# CPU.net
KiCad netlist of a schematic drawn in Altium Designer
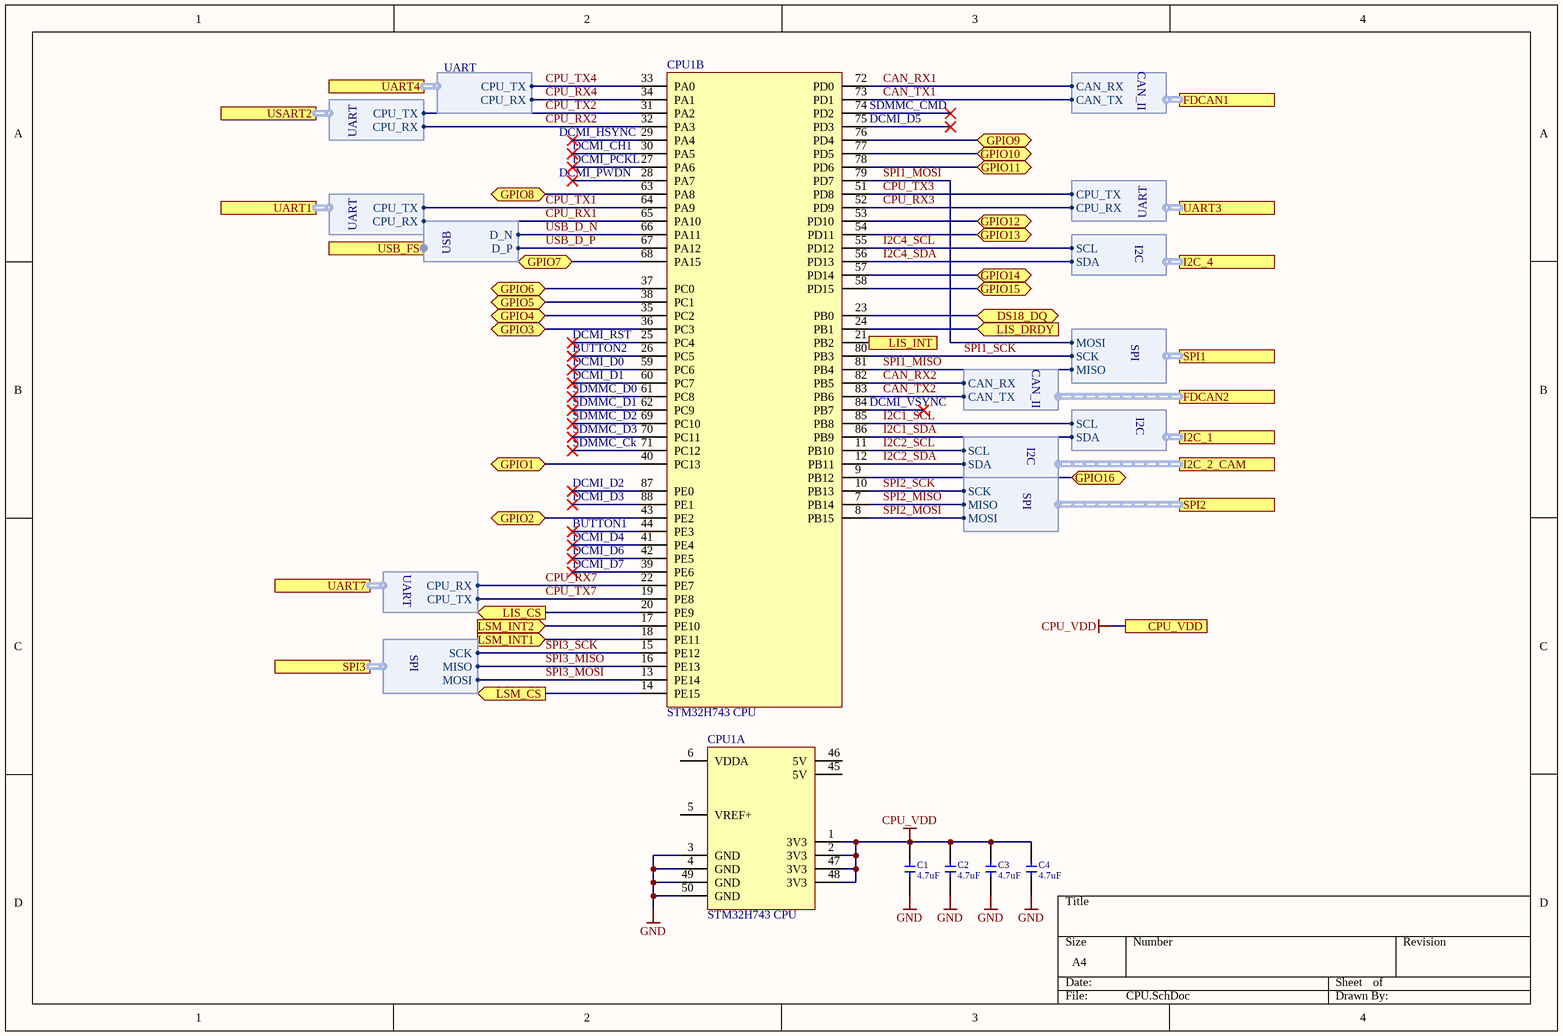
[diagram p0: CPU.SchDoc]

(export (version "E")
  (design (tool "Eeschema 10.0.6"))
  (components
    (comp (ref "C1")
      (value "4.7uF")
      (footprint "CERCAP 0603")
      (description "Capacitor")
      (fields (field (name "Comment") "CERCAP 0603 4.7uF * X7R"))
      (libsource (lib "!main") (part "!Capacitor"))
    )
    (comp (ref "C2")
      (value "4.7uF")
      (footprint "CERCAP 0603")
      (description "Capacitor")
      (fields (field (name "Comment") "CERCAP 0603 4.7uF * X7R"))
      (libsource (lib "!main") (part "!Capacitor"))
    )
    (comp (ref "C3")
      (value "4.7uF")
      (footprint "CERCAP 0603")
      (description "Capacitor")
      (fields (field (name "Comment") "CERCAP 0603 4.7uF * X7R"))
      (libsource (lib "!main") (part "!Capacitor"))
    )
    (comp (ref "C4")
      (value "4.7uF")
      (footprint "CERCAP 0603")
      (description "Capacitor")
      (fields (field (name "Comment") "CERCAP 0603 4.7uF * X7R"))
      (libsource (lib "!main") (part "!Capacitor"))
    )
    (comp (ref "CPU1")
      (value "STM32H743 CPU")
      (footprint "STM32H7_CPU")
      (description "STM32H743 processor module")
      (libsource (lib "modules") (part "STM32H7 CPU"))
    )
  )
  (nets
    (net (code "6") (name "/CAN_RX1") (class "Default")
      (node (ref "CPU1") (pin "72") (pinfunction "PD0_72") (pintype "passive"))
    )
    (net (code "7") (name "/CAN_RX2") (class "Default")
      (node (ref "CPU1") (pin "82") (pinfunction "PB5_82") (pintype "passive"))
    )
    (net (code "8") (name "/CAN_TX1") (class "Default")
      (node (ref "CPU1") (pin "73") (pinfunction "PD1_73") (pintype "passive"))
    )
    (net (code "9") (name "/CAN_TX2") (class "Default")
      (node (ref "CPU1") (pin "83") (pinfunction "PB6_83") (pintype "passive"))
    )
    (net (code "10") (name "/CPU_RX1") (class "Default")
      (node (ref "CPU1") (pin "65") (pinfunction "PA10_65") (pintype "passive"))
    )
    (net (code "11") (name "/CPU_RX2") (class "Default")
      (node (ref "CPU1") (pin "32") (pinfunction "PA3_32") (pintype "passive"))
    )
    (net (code "12") (name "/CPU_RX3") (class "Default")
      (node (ref "CPU1") (pin "52") (pinfunction "PD9_52") (pintype "passive"))
    )
    (net (code "13") (name "/CPU_RX4") (class "Default")
      (node (ref "CPU1") (pin "34") (pinfunction "PA1_34") (pintype "passive"))
    )
    (net (code "14") (name "/CPU_RX7") (class "Default")
      (node (ref "CPU1") (pin "22") (pinfunction "PE7_22") (pintype "passive"))
    )
    (net (code "15") (name "/CPU_TX1") (class "Default")
      (node (ref "CPU1") (pin "64") (pinfunction "PA9_64") (pintype "passive"))
    )
    (net (code "16") (name "/CPU_TX2") (class "Default")
      (node (ref "CPU1") (pin "31") (pinfunction "PA2_31") (pintype "passive"))
    )
    (net (code "17") (name "/CPU_TX3") (class "Default")
      (node (ref "CPU1") (pin "51") (pinfunction "PD8_51") (pintype "passive"))
    )
    (net (code "18") (name "/CPU_TX4") (class "Default")
      (node (ref "CPU1") (pin "33") (pinfunction "PA0_33") (pintype "passive"))
    )
    (net (code "19") (name "/CPU_TX7") (class "Default")
      (node (ref "CPU1") (pin "19") (pinfunction "PE8_19") (pintype "passive"))
    )
    (net (code "20") (name "/DS18_DQ") (class "Default")
      (node (ref "CPU1") (pin "23") (pinfunction "PB0_23") (pintype "passive"))
    )
    (net (code "21") (name "/GPIO1") (class "Default")
      (node (ref "CPU1") (pin "40") (pinfunction "PC13_40") (pintype "passive"))
    )
    (net (code "22") (name "/GPIO2") (class "Default")
      (node (ref "CPU1") (pin "43") (pinfunction "PE2_43") (pintype "passive"))
    )
    (net (code "23") (name "/GPIO3") (class "Default")
      (node (ref "CPU1") (pin "36") (pinfunction "PC3_36") (pintype "passive"))
    )
    (net (code "24") (name "/GPIO4") (class "Default")
      (node (ref "CPU1") (pin "35") (pinfunction "PC2_35") (pintype "passive"))
    )
    (net (code "25") (name "/GPIO5") (class "Default")
      (node (ref "CPU1") (pin "38") (pinfunction "PC1_38") (pintype "passive"))
    )
    (net (code "26") (name "/GPIO6") (class "Default")
      (node (ref "CPU1") (pin "37") (pinfunction "PC0_37") (pintype "passive"))
    )
    (net (code "27") (name "/GPIO7") (class "Default")
      (node (ref "CPU1") (pin "68") (pinfunction "PA15_68") (pintype "passive"))
    )
    (net (code "28") (name "/GPIO8") (class "Default")
      (node (ref "CPU1") (pin "63") (pinfunction "PA8_63") (pintype "passive"))
    )
    (net (code "29") (name "/GPIO9") (class "Default")
      (node (ref "CPU1") (pin "76") (pinfunction "PD4_76") (pintype "passive"))
    )
    (net (code "30") (name "/GPIO10") (class "Default")
      (node (ref "CPU1") (pin "77") (pinfunction "PD5_77") (pintype "passive"))
    )
    (net (code "31") (name "/GPIO11") (class "Default")
      (node (ref "CPU1") (pin "78") (pinfunction "PD6_78") (pintype "passive"))
    )
    (net (code "32") (name "/GPIO12") (class "Default")
      (node (ref "CPU1") (pin "53") (pinfunction "PD10_53") (pintype "passive"))
    )
    (net (code "33") (name "/GPIO13") (class "Default")
      (node (ref "CPU1") (pin "54") (pinfunction "PD11_54") (pintype "passive"))
    )
    (net (code "34") (name "/GPIO14") (class "Default")
      (node (ref "CPU1") (pin "57") (pinfunction "PD14_57") (pintype "passive"))
    )
    (net (code "35") (name "/GPIO15") (class "Default")
      (node (ref "CPU1") (pin "58") (pinfunction "PD15_58") (pintype "passive"))
    )
    (net (code "36") (name "/GPIO16") (class "Default")
      (node (ref "CPU1") (pin "9") (pinfunction "PB12_9") (pintype "passive"))
    )
    (net (code "37") (name "/I2C1_SCL") (class "Default")
      (node (ref "CPU1") (pin "85") (pinfunction "PB8_85") (pintype "passive"))
    )
    (net (code "38") (name "/I2C1_SDA") (class "Default")
      (node (ref "CPU1") (pin "86") (pinfunction "PB9_86") (pintype "passive"))
    )
    (net (code "39") (name "/I2C2_SCL") (class "Default")
      (node (ref "CPU1") (pin "11") (pinfunction "PB10_11") (pintype "passive"))
    )
    (net (code "40") (name "/I2C2_SDA") (class "Default")
      (node (ref "CPU1") (pin "12") (pinfunction "PB11_12") (pintype "passive"))
    )
    (net (code "41") (name "/I2C4_SCL") (class "Default")
      (node (ref "CPU1") (pin "55") (pinfunction "PD12_55") (pintype "passive"))
    )
    (net (code "42") (name "/I2C4_SDA") (class "Default")
      (node (ref "CPU1") (pin "56") (pinfunction "PD13_56") (pintype "passive"))
    )
    (net (code "43") (name "/LIS_CS") (class "Default")
      (node (ref "CPU1") (pin "20") (pinfunction "PE9_20") (pintype "passive"))
    )
    (net (code "44") (name "/LIS_DRDY") (class "Default")
      (node (ref "CPU1") (pin "24") (pinfunction "PB1_24") (pintype "passive"))
    )
    (net (code "45") (name "/LIS_INT") (class "Default")
      (node (ref "CPU1") (pin "21") (pinfunction "PB2_21") (pintype "passive"))
    )
    (net (code "46") (name "/LSM_CS") (class "Default")
      (node (ref "CPU1") (pin "14") (pinfunction "PE15_14") (pintype "passive"))
    )
    (net (code "47") (name "/LSM_INT1") (class "Default")
      (node (ref "CPU1") (pin "18") (pinfunction "PE11_18") (pintype "passive"))
    )
    (net (code "48") (name "/LSM_INT2") (class "Default")
      (node (ref "CPU1") (pin "17") (pinfunction "PE10_17") (pintype "passive"))
    )
    (net (code "49") (name "/SPI1_MISO") (class "Default")
      (node (ref "CPU1") (pin "81") (pinfunction "PB4_81") (pintype "passive"))
    )
    (net (code "50") (name "/SPI1_MOSI") (class "Default")
      (node (ref "CPU1") (pin "79") (pinfunction "PD7_79") (pintype "passive"))
    )
    (net (code "51") (name "/SPI1_SCK") (class "Default")
      (node (ref "CPU1") (pin "80") (pinfunction "PB3_80") (pintype "passive"))
    )
    (net (code "52") (name "/SPI2_MISO") (class "Default")
      (node (ref "CPU1") (pin "7") (pinfunction "PB14_7") (pintype "passive"))
    )
    (net (code "53") (name "/SPI2_MOSI") (class "Default")
      (node (ref "CPU1") (pin "8") (pinfunction "PB15_8") (pintype "passive"))
    )
    (net (code "54") (name "/SPI2_SCK") (class "Default")
      (node (ref "CPU1") (pin "10") (pinfunction "PB13_10") (pintype "passive"))
    )
    (net (code "55") (name "/SPI3_MISO") (class "Default")
      (node (ref "CPU1") (pin "16") (pinfunction "PE13_16") (pintype "passive"))
    )
    (net (code "56") (name "/SPI3_MOSI") (class "Default")
      (node (ref "CPU1") (pin "13") (pinfunction "PE14_13") (pintype "passive"))
    )
    (net (code "57") (name "/SPI3_SCK") (class "Default")
      (node (ref "CPU1") (pin "15") (pinfunction "PE12_15") (pintype "passive"))
    )
    (net (code "58") (name "/USB_D_N") (class "Default")
      (node (ref "CPU1") (pin "66") (pinfunction "PA11_66") (pintype "passive"))
    )
    (net (code "59") (name "/USB_D_P") (class "Default")
      (node (ref "CPU1") (pin "67") (pinfunction "PA12_67") (pintype "passive"))
    )
    (net (code "65") (name "CPU_VDD") (class "Default")
      (node (ref "C1") (pin "2") (pintype "passive"))
      (node (ref "C2") (pin "2") (pintype "passive"))
      (node (ref "C3") (pin "2") (pintype "passive"))
      (node (ref "C4") (pin "2") (pintype "passive"))
      (node (ref "CPU1") (pin "1") (pinfunction "3V3_1") (pintype "passive"))
      (node (ref "CPU1") (pin "2") (pinfunction "3V3_2") (pintype "passive"))
      (node (ref "CPU1") (pin "47") (pinfunction "3V3_47") (pintype "passive"))
      (node (ref "CPU1") (pin "48") (pinfunction "3V3_48") (pintype "passive"))
    )
    (net (code "66") (name "GND") (class "Default")
      (node (ref "C1") (pin "1") (pintype "passive"))
      (node (ref "C2") (pin "1") (pintype "passive"))
      (node (ref "C3") (pin "1") (pintype "passive"))
      (node (ref "C4") (pin "1") (pintype "passive"))
      (node (ref "CPU1") (pin "3") (pinfunction "GND_3") (pintype "passive"))
      (node (ref "CPU1") (pin "4") (pinfunction "GND_4") (pintype "passive"))
      (node (ref "CPU1") (pin "49") (pinfunction "GND_49") (pintype "passive"))
      (node (ref "CPU1") (pin "50") (pinfunction "GND_50") (pintype "passive"))
    )
    (net (code "67") (name "unconnected-(CPU1A-5V-Pad45)") (class "Default")
      (node (ref "CPU1") (pin "45") (pinfunction "5V_45") (pintype "passive"))
    )
    (net (code "68") (name "unconnected-(CPU1A-5V-Pad46)") (class "Default")
      (node (ref "CPU1") (pin "46") (pinfunction "5V_46") (pintype "passive"))
    )
    (net (code "69") (name "unconnected-(CPU1A-VDDA-Pad6)") (class "Default")
      (node (ref "CPU1") (pin "6") (pinfunction "VDDA_6") (pintype "passive"))
    )
    (net (code "70") (name "unconnected-(CPU1A-VREF+-Pad5)") (class "Default")
      (node (ref "CPU1") (pin "5") (pinfunction "VREF+_5") (pintype "passive"))
    )
    (net (code "71") (name "unconnected-(CPU1B-PA4-Pad29)") (class "Default")
      (node (ref "CPU1") (pin "29") (pinfunction "PA4_29") (pintype "passive+no_connect"))
    )
    (net (code "72") (name "unconnected-(CPU1B-PA5-Pad30)") (class "Default")
      (node (ref "CPU1") (pin "30") (pinfunction "PA5_30") (pintype "passive+no_connect"))
    )
    (net (code "73") (name "unconnected-(CPU1B-PA6-Pad27)") (class "Default")
      (node (ref "CPU1") (pin "27") (pinfunction "PA6_27") (pintype "passive+no_connect"))
    )
    (net (code "74") (name "unconnected-(CPU1B-PA7-Pad28)") (class "Default")
      (node (ref "CPU1") (pin "28") (pinfunction "PA7_28") (pintype "passive+no_connect"))
    )
    (net (code "75") (name "unconnected-(CPU1B-PB7-Pad84)") (class "Default")
      (node (ref "CPU1") (pin "84") (pinfunction "PB7_84") (pintype "passive+no_connect"))
    )
    (net (code "76") (name "unconnected-(CPU1B-PC4-Pad25)") (class "Default")
      (node (ref "CPU1") (pin "25") (pinfunction "PC4_25") (pintype "passive+no_connect"))
    )
    (net (code "77") (name "unconnected-(CPU1B-PC5-Pad26)") (class "Default")
      (node (ref "CPU1") (pin "26") (pinfunction "PC5_26") (pintype "passive+no_connect"))
    )
    (net (code "78") (name "unconnected-(CPU1B-PC6-Pad59)") (class "Default")
      (node (ref "CPU1") (pin "59") (pinfunction "PC6_59") (pintype "passive+no_connect"))
    )
    (net (code "79") (name "unconnected-(CPU1B-PC7-Pad60)") (class "Default")
      (node (ref "CPU1") (pin "60") (pinfunction "PC7_60") (pintype "passive+no_connect"))
    )
    (net (code "80") (name "unconnected-(CPU1B-PC8-Pad61)") (class "Default")
      (node (ref "CPU1") (pin "61") (pinfunction "PC8_61") (pintype "passive+no_connect"))
    )
    (net (code "81") (name "unconnected-(CPU1B-PC9-Pad62)") (class "Default")
      (node (ref "CPU1") (pin "62") (pinfunction "PC9_62") (pintype "passive+no_connect"))
    )
    (net (code "82") (name "unconnected-(CPU1B-PC10-Pad69)") (class "Default")
      (node (ref "CPU1") (pin "69") (pinfunction "PC10_69") (pintype "passive+no_connect"))
    )
    (net (code "83") (name "unconnected-(CPU1B-PC11-Pad70)") (class "Default")
      (node (ref "CPU1") (pin "70") (pinfunction "PC11_70") (pintype "passive+no_connect"))
    )
    (net (code "84") (name "unconnected-(CPU1B-PC12-Pad71)") (class "Default")
      (node (ref "CPU1") (pin "71") (pinfunction "PC12_71") (pintype "passive+no_connect"))
    )
    (net (code "85") (name "unconnected-(CPU1B-PD2-Pad74)") (class "Default")
      (node (ref "CPU1") (pin "74") (pinfunction "PD2_74") (pintype "passive+no_connect"))
    )
    (net (code "86") (name "unconnected-(CPU1B-PD3-Pad75)") (class "Default")
      (node (ref "CPU1") (pin "75") (pinfunction "PD3_75") (pintype "passive+no_connect"))
    )
    (net (code "87") (name "unconnected-(CPU1B-PE0-Pad87)") (class "Default")
      (node (ref "CPU1") (pin "87") (pinfunction "PE0_87") (pintype "passive+no_connect"))
    )
    (net (code "88") (name "unconnected-(CPU1B-PE1-Pad88)") (class "Default")
      (node (ref "CPU1") (pin "88") (pinfunction "PE1_88") (pintype "passive+no_connect"))
    )
    (net (code "89") (name "unconnected-(CPU1B-PE3-Pad44)") (class "Default")
      (node (ref "CPU1") (pin "44") (pinfunction "PE3_44") (pintype "passive+no_connect"))
    )
    (net (code "90") (name "unconnected-(CPU1B-PE4-Pad41)") (class "Default")
      (node (ref "CPU1") (pin "41") (pinfunction "PE4_41") (pintype "passive+no_connect"))
    )
    (net (code "91") (name "unconnected-(CPU1B-PE5-Pad42)") (class "Default")
      (node (ref "CPU1") (pin "42") (pinfunction "PE5_42") (pintype "passive+no_connect"))
    )
    (net (code "92") (name "unconnected-(CPU1B-PE6-Pad39)") (class "Default")
      (node (ref "CPU1") (pin "39") (pinfunction "PE6_39") (pintype "passive+no_connect"))
    )
  )
)
